# CP2102_UART.net
KiCad netlist of a schematic drawn in Altium Designer
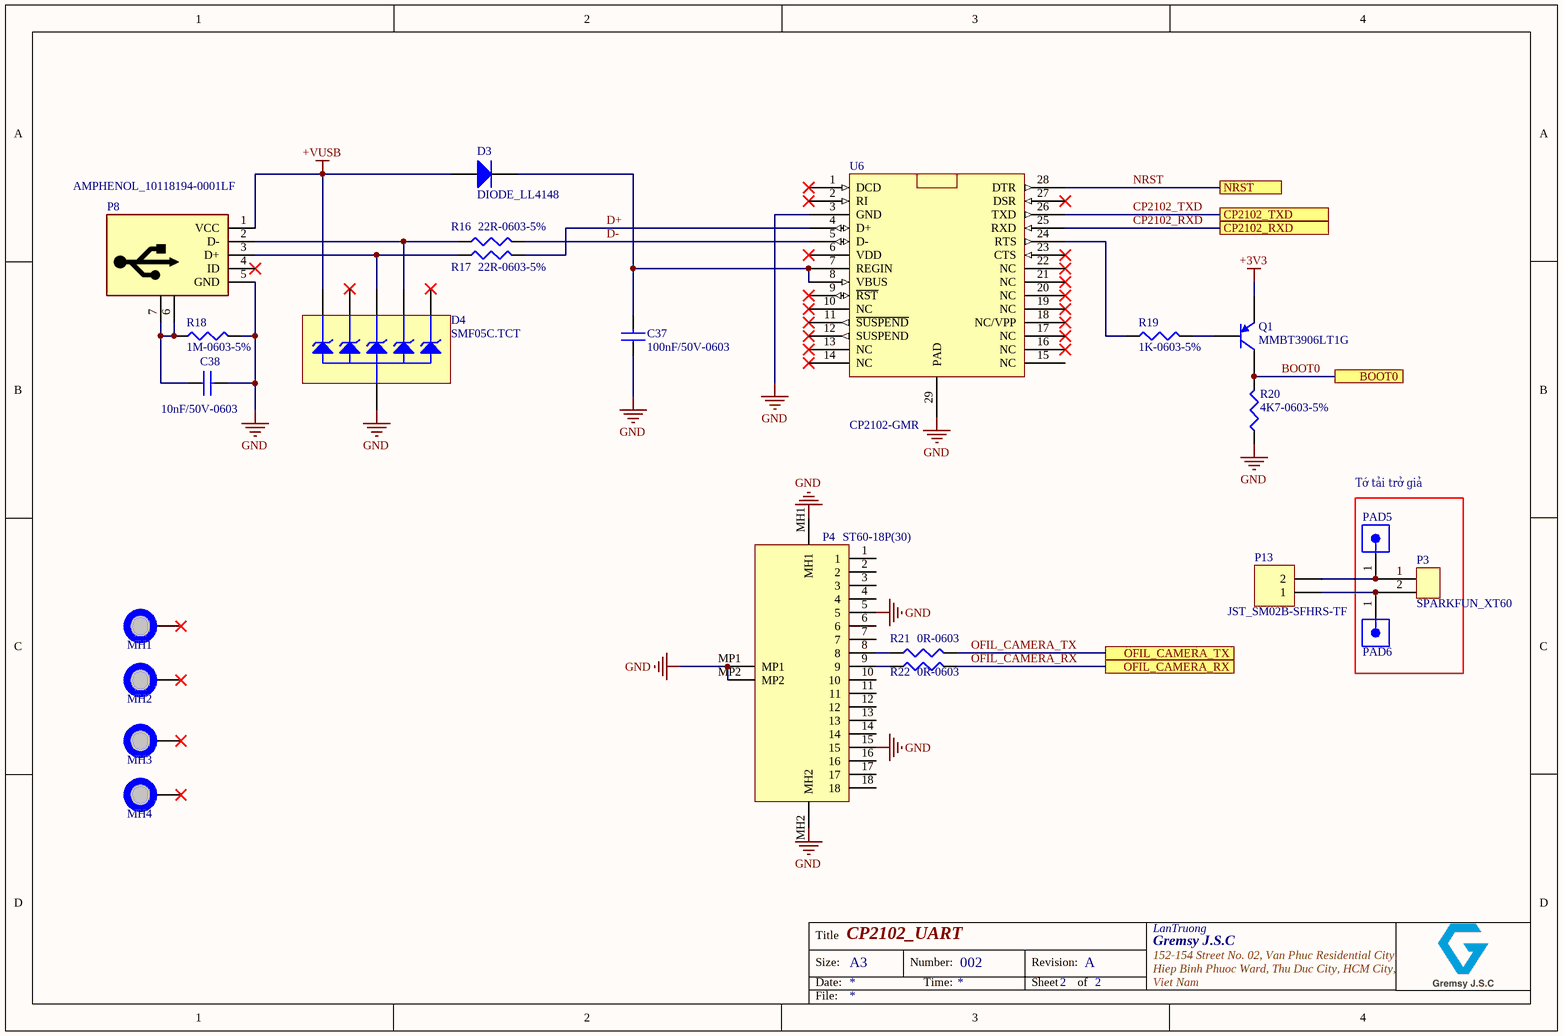
[diagram p0: CP2102_UART.SchDoc]

(export (version "E")
  (design (tool "Eeschema 10.0.6"))
  (components
    (comp (ref "C37")
      (value "100nF/50V-0603")
      (footprint "CAP0603")
      (description "CAP CER 0.1UF 50V X7R 0603")
      (fields (field (name "TOLERANCE") "±10%"))
      (libsource (lib "GremsyJSC") (part "CAP_100nF/50V-0603-10%"))
    )
    (comp (ref "C38")
      (value "10nF/50V-0603")
      (footprint "CAP0603")
      (description "CAP CER 10000PF 50V X7R 0603")
      (fields (field (name "TOLERANCE") "±10%"))
      (libsource (lib "GremsyJSC") (part "CAP_10nF/50V-0603-10%"))
    )
    (comp (ref "D3")
      (value "DIODE_LL4148")
      (footprint "SOD80")
      (description "DIODE GEN PURP 100V 200MA SOD80")
      (fields (field (name "MANUFACTURER") "Fairchild/ON Semiconductor"))
      (libsource (lib "GremsyJSC") (part "DIODE-RECTIFIER_LL4148"))
    )
    (comp (ref "D4")
      (value "SMF05C.TCT")
      (footprint "SC-88")
      (description "TVS DIODE 5VWM 12.5VC SC70-6")
      (libsource (lib "GremsyJSC") (part "DIODE-ESD_SMF05C.TCT"))
    )
    (comp (ref "MH1")
      (value "MH_3MMC_2.1MMD")
      (footprint "MH_3MMD_2.1MMD")
      (description "Mounting Hole 3mm Diameter, 2.1mm Drill")
      (libsource (lib "GremsyJSC") (part "MH_3MMC_2.1MMD"))
    )
    (comp (ref "MH2")
      (value "MH_3MMC_2.1MMD")
      (footprint "MH_3MMD_2.1MMD")
      (description "Mounting Hole 3mm Diameter, 2.1mm Drill")
      (libsource (lib "GremsyJSC") (part "MH_3MMC_2.1MMD"))
    )
    (comp (ref "MH3")
      (value "MH_3MMC_2.1MMD")
      (footprint "MH_3MMD_2.1MMD")
      (description "Mounting Hole 3mm Diameter, 2.1mm Drill")
      (libsource (lib "GremsyJSC") (part "MH_3MMC_2.1MMD"))
    )
    (comp (ref "MH4")
      (value "MH_3MMC_2.1MMD")
      (footprint "MH_3MMD_2.1MMD")
      (description "Mounting Hole 3mm Diameter, 2.1mm Drill")
      (libsource (lib "GremsyJSC") (part "MH_3MMC_2.1MMD"))
    )
    (comp (ref "P3")
      (value "SPARKFUN_XT60")
      (footprint "GremsyJSC:XT60_MALE_RA")
      (description "CON XT-60, MALE PIN, THROUGH HOLE, 500V, 30A")
      (fields (field (name "MANUFACTURER") "SparkFun Electronics"))
      (libsource (lib "GremsyJSC") (part "CON-SPARKFUN_XT60"))
    )
    (comp (ref "P4")
      (value "ST60-18P(30)")
      (footprint "GremsyJSC:ST6018P30")
      (description "HEADER 18POS PITCH 0.5MM, SMD, ST, FEMALE")
      (libsource (lib "GremsyJSC") (part "CON-HIROSE_ST60-18P(30)"))
    )
    (comp (ref "P8")
      (value "AMPHENOL_10118194-0001LF")
      (footprint "USB-B-Micro_10118194-0001LF")
      (description "USB2.0 MICRO_5POS-RA-SMD-F-AM, FEMALE")
      (libsource (lib "GremsyJSC") (part "CON-AMPHENOL_10118194-0001LF"))
    )
    (comp (ref "P13")
      (value "JST_SM02B-SFHRS-TF")
      (footprint "JST_M02B-SFHRS-TF(LF)(SN)")
      (description "PWR_2POS-P1.8-RA-SMD-M")
      (fields (field (name "MANUFACTURER") "JST"))
      (libsource (lib "GremsyJSC") (part "CON-JST_SM02B-SFHRS-TF"))
    )
    (comp (ref "PAD5")
      (value "PAD_2.5MM_1.5MM")
      (footprint "PAD_2.5MM_1.5MM_HOLE")
      (description "PAD_2.5MMC_1.5MMD_HOLE")
      (libsource (lib "GremsyJSC") (part "PAD_2.5MMC_1.5MMD_HOLE"))
    )
    (comp (ref "PAD6")
      (value "PAD_2.5MM_1.5MM")
      (footprint "PAD_2.5MM_1.5MM_HOLE")
      (description "PAD_2.5MMC_1.5MMD_HOLE")
      (libsource (lib "GremsyJSC") (part "PAD_2.5MMC_1.5MMD_HOLE"))
    )
    (comp (ref "Q1")
      (value "MMBT3906LT1G")
      (footprint "SOT23")
      (description "TRANS PNP 40V 0.2A SOT23")
      (fields (field (name "TOLERANCE") "±10%"))
      (libsource (lib "GremsyJSC") (part "TRNS-PNP_MMBT3906LT1G"))
    )
    (comp (ref "R16")
      (value "22R-0603-5%")
      (footprint "RES0603")
      (description "RES 22 OHM 5% 1/10W 0603")
      (fields (field (name "TOLERANCE") "±5%"))
      (libsource (lib "GremsyJSC") (part "RES_22R-0603-5%"))
    )
    (comp (ref "R17")
      (value "22R-0603-5%")
      (footprint "RES0603")
      (description "RES 22 OHM 5% 1/10W 0603")
      (fields (field (name "TOLERANCE") "±5%"))
      (libsource (lib "GremsyJSC") (part "RES_22R-0603-5%"))
    )
    (comp (ref "R18")
      (value "1M-0603-5%")
      (footprint "RES0603")
      (description "RES 1M OHM 5% 1/10W 0603")
      (fields (field (name "TOLERANCE") "±5%"))
      (libsource (lib "GremsyJSC") (part "RES_1M-0603-5%"))
    )
    (comp (ref "R19")
      (value "1K-0603-5%")
      (footprint "RES0603")
      (description "RES 1K OHM 5% 1/10W 0603")
      (fields (field (name "TOLERANCE") "±5%"))
      (libsource (lib "GremsyJSC") (part "RES_1K-0603-5%"))
    )
    (comp (ref "R20")
      (value "4K7-0603-5%")
      (footprint "RES0603")
      (description "RES 4.7K OHM 5% 1/10W 0603")
      (fields (field (name "MANUFACTURER") "Yageo") (field (name "TOLERANCE") "±5%"))
      (libsource (lib "GremsyJSC") (part "RES_4K7-0603-5%"))
    )
    (comp (ref "R21")
      (value "0R-0603")
      (footprint "RES0603")
      (description "RES 0 OHM JUMPER 1/10W 0603")
      (fields (field (name "TOLERANCE") "Jumper"))
      (libsource (lib "GremsyJSC") (part "RES_0R-0603"))
    )
    (comp (ref "R22")
      (value "0R-0603")
      (footprint "RES0603")
      (description "RES 0 OHM JUMPER 1/10W 0603")
      (fields (field (name "TOLERANCE") "Jumper"))
      (libsource (lib "GremsyJSC") (part "RES_0R-0603"))
    )
    (comp (ref "U6")
      (value "CP2102-GMR")
      (footprint "QFN28-Pitch 0.5 mm")
      (description "IC USB-TO-UART BRIDGE 28VQFN")
      (libsource (lib "GremsyCo") (part "CP2102-GMR"))
    )
  )
  (nets
    (net (code "1") (name "+3V3") (class "Default")
      (node (ref "Q1") (pin "2") (pinfunction "E_2") (pintype "passive"))
    )
    (net (code "2") (name "+VUSB") (class "Default")
      (node (ref "D3") (pin "1") (pinfunction "A_1") (pintype "passive"))
      (node (ref "D4") (pin "1") (pintype "passive"))
      (node (ref "P8") (pin "1") (pinfunction "VCC_1") (pintype "passive"))
    )
    (net (code "3") (name "/BOOT0") (class "Default")
      (node (ref "Q1") (pin "3") (pinfunction "C_3") (pintype "passive"))
      (node (ref "R20") (pin "2") (pinfunction "2_2") (pintype "passive"))
    )
    (net (code "4") (name "/CP2102_RXD") (class "Default")
      (node (ref "U6") (pin "25") (pinfunction "RXD_25") (pintype "input"))
    )
    (net (code "5") (name "/CP2102_TXD") (class "Default")
      (node (ref "U6") (pin "26") (pinfunction "TXD_26") (pintype "output"))
    )
    (net (code "6") (name "/D+") (class "Default")
      (node (ref "R17") (pin "2") (pinfunction "2_2") (pintype "passive"))
      (node (ref "U6") (pin "4") (pinfunction "D+_4") (pintype "bidirectional"))
    )
    (net (code "7") (name "/D-") (class "Default")
      (node (ref "R16") (pin "2") (pinfunction "2_2") (pintype "passive"))
      (node (ref "U6") (pin "5") (pinfunction "D-_5") (pintype "bidirectional"))
    )
    (net (code "8") (name "/NRST") (class "Default")
      (node (ref "U6") (pin "28") (pinfunction "DTR_28") (pintype "output"))
    )
    (net (code "9") (name "/OFIL_CAMERA_RX") (class "Default")
      (node (ref "R22") (pin "2") (pinfunction "2_2") (pintype "passive"))
    )
    (net (code "10") (name "/OFIL_CAMERA_TX") (class "Default")
      (node (ref "R21") (pin "2") (pinfunction "2_2") (pintype "passive"))
    )
    (net (code "11") (name "GND") (class "Default")
      (node (ref "C37") (pin "1") (pinfunction "1_1") (pintype "passive"))
      (node (ref "C38") (pin "2") (pinfunction "2_2") (pintype "passive"))
      (node (ref "D4") (pin "2") (pintype "passive"))
      (node (ref "P4") (pin "15") (pinfunction "15_15") (pintype "passive"))
      (node (ref "P4") (pin "5") (pinfunction "5_5") (pintype "passive"))
      (node (ref "P4") (pin "MH1") (pinfunction "MH1_MH1") (pintype "passive"))
      (node (ref "P4") (pin "MH2") (pinfunction "MH2_MH2") (pintype "passive"))
      (node (ref "P4") (pin "MP1") (pinfunction "MP1_MP1") (pintype "passive"))
      (node (ref "P4") (pin "MP2") (pinfunction "MP2_MP2") (pintype "passive"))
      (node (ref "P8") (pin "5") (pinfunction "GND_5") (pintype "passive"))
      (node (ref "R18") (pin "2") (pinfunction "2_2") (pintype "passive"))
      (node (ref "R20") (pin "1") (pinfunction "1_1") (pintype "passive"))
      (node (ref "U6") (pin "29") (pinfunction "PAD_29") (pintype "power_in"))
      (node (ref "U6") (pin "3") (pinfunction "GND_3") (pintype "power_in"))
    )
    (net (code "12") (name "Net-(C38-Pad1)") (class "Default")
      (node (ref "C38") (pin "1") (pinfunction "1_1") (pintype "passive"))
      (node (ref "P8") (pin "6") (pinfunction "SHIELD_6") (pintype "passive"))
      (node (ref "P8") (pin "7") (pinfunction "SHIELD_7") (pintype "power_in"))
      (node (ref "R18") (pin "1") (pinfunction "1_1") (pintype "passive"))
    )
    (net (code "13") (name "Net-(D3-K)") (class "Default")
      (node (ref "C37") (pin "2") (pinfunction "2_2") (pintype "passive"))
      (node (ref "D3") (pin "2") (pinfunction "K_2") (pintype "passive"))
      (node (ref "U6") (pin "7") (pinfunction "REGIN_7") (pintype "power_in"))
      (node (ref "U6") (pin "8") (pinfunction "VBUS_8") (pintype "input"))
    )
    (net (code "14") (name "Net-(P4-Pad8)") (class "Default")
      (node (ref "P4") (pin "8") (pinfunction "8_8") (pintype "passive"))
      (node (ref "R21") (pin "1") (pinfunction "1_1") (pintype "passive"))
    )
    (net (code "15") (name "Net-(P4-Pad9)") (class "Default")
      (node (ref "P4") (pin "9") (pinfunction "9_9") (pintype "passive"))
      (node (ref "R22") (pin "1") (pinfunction "1_1") (pintype "passive"))
    )
    (net (code "16") (name "Net-(P8-D+)") (class "Default")
      (node (ref "D4") (pin "4") (pintype "passive"))
      (node (ref "P8") (pin "3") (pinfunction "D+_3") (pintype "passive"))
      (node (ref "R17") (pin "1") (pinfunction "1_1") (pintype "passive"))
    )
    (net (code "17") (name "Net-(P8-D-)") (class "Default")
      (node (ref "D4") (pin "5") (pintype "passive"))
      (node (ref "P8") (pin "2") (pinfunction "D-_2") (pintype "passive"))
      (node (ref "R16") (pin "1") (pinfunction "1_1") (pintype "passive"))
    )
    (net (code "18") (name "Net-(P13-Pad1)") (class "Default")
      (node (ref "P13") (pin "1") (pinfunction "1_1") (pintype "passive"))
      (node (ref "P3") (pin "2") (pinfunction "2_2") (pintype "passive"))
      (node (ref "PAD6") (pin "1") (pinfunction "1_1") (pintype "passive"))
    )
    (net (code "19") (name "Net-(P13-Pad2)") (class "Default")
      (node (ref "P13") (pin "2") (pinfunction "2_2") (pintype "passive"))
      (node (ref "P3") (pin "1") (pinfunction "1_1") (pintype "passive"))
      (node (ref "PAD5") (pin "1") (pinfunction "1_1") (pintype "passive"))
    )
    (net (code "20") (name "Net-(Q1-B)") (class "Default")
      (node (ref "Q1") (pin "1") (pinfunction "B_1") (pintype "passive"))
      (node (ref "R19") (pin "2") (pinfunction "2_2") (pintype "passive"))
    )
    (net (code "21") (name "Net-(U6-RTS)") (class "Default")
      (node (ref "R19") (pin "1") (pinfunction "1_1") (pintype "passive"))
      (node (ref "U6") (pin "24") (pinfunction "RTS_24") (pintype "output"))
    )
    (net (code "22") (name "unconnected-(D4-Pad3)") (class "Default")
      (node (ref "D4") (pin "3") (pintype "passive+no_connect"))
    )
    (net (code "23") (name "unconnected-(D4-Pad6)") (class "Default")
      (node (ref "D4") (pin "6") (pintype "passive+no_connect"))
    )
    (net (code "24") (name "unconnected-(MH1-Pad1)") (class "Default")
      (node (ref "MH1") (pin "1") (pinfunction "1_1") (pintype "passive+no_connect"))
    )
    (net (code "25") (name "unconnected-(MH2-Pad1)") (class "Default")
      (node (ref "MH2") (pin "1") (pinfunction "1_1") (pintype "passive+no_connect"))
    )
    (net (code "26") (name "unconnected-(MH3-Pad1)") (class "Default")
      (node (ref "MH3") (pin "1") (pinfunction "1_1") (pintype "passive+no_connect"))
    )
    (net (code "27") (name "unconnected-(MH4-Pad1)") (class "Default")
      (node (ref "MH4") (pin "1") (pinfunction "1_1") (pintype "passive+no_connect"))
    )
    (net (code "28") (name "unconnected-(P4-Pad1)") (class "Default")
      (node (ref "P4") (pin "1") (pinfunction "1_1") (pintype "passive"))
    )
    (net (code "29") (name "unconnected-(P4-Pad2)") (class "Default")
      (node (ref "P4") (pin "2") (pinfunction "2_2") (pintype "passive"))
    )
    (net (code "30") (name "unconnected-(P4-Pad3)") (class "Default")
      (node (ref "P4") (pin "3") (pinfunction "3_3") (pintype "passive"))
    )
    (net (code "31") (name "unconnected-(P4-Pad4)") (class "Default")
      (node (ref "P4") (pin "4") (pinfunction "4_4") (pintype "passive"))
    )
    (net (code "32") (name "unconnected-(P4-Pad6)") (class "Default")
      (node (ref "P4") (pin "6") (pinfunction "6_6") (pintype "passive"))
    )
    (net (code "33") (name "unconnected-(P4-Pad7)") (class "Default")
      (node (ref "P4") (pin "7") (pinfunction "7_7") (pintype "passive"))
    )
    (net (code "34") (name "unconnected-(P4-Pad10)") (class "Default")
      (node (ref "P4") (pin "10") (pinfunction "10_10") (pintype "passive"))
    )
    (net (code "35") (name "unconnected-(P4-Pad11)") (class "Default")
      (node (ref "P4") (pin "11") (pinfunction "11_11") (pintype "passive"))
    )
    (net (code "36") (name "unconnected-(P4-Pad12)") (class "Default")
      (node (ref "P4") (pin "12") (pinfunction "12_12") (pintype "passive"))
    )
    (net (code "37") (name "unconnected-(P4-Pad13)") (class "Default")
      (node (ref "P4") (pin "13") (pinfunction "13_13") (pintype "passive"))
    )
    (net (code "38") (name "unconnected-(P4-Pad14)") (class "Default")
      (node (ref "P4") (pin "14") (pinfunction "14_14") (pintype "passive"))
    )
    (net (code "39") (name "unconnected-(P4-Pad16)") (class "Default")
      (node (ref "P4") (pin "16") (pinfunction "16_16") (pintype "passive"))
    )
    (net (code "40") (name "unconnected-(P4-Pad17)") (class "Default")
      (node (ref "P4") (pin "17") (pinfunction "17_17") (pintype "passive"))
    )
    (net (code "41") (name "unconnected-(P4-Pad18)") (class "Default")
      (node (ref "P4") (pin "18") (pinfunction "18_18") (pintype "passive"))
    )
    (net (code "42") (name "unconnected-(P8-ID-Pad4)") (class "Default")
      (node (ref "P8") (pin "4") (pinfunction "ID_4") (pintype "passive+no_connect"))
    )
    (net (code "43") (name "unconnected-(U6-CTS-Pad23)") (class "Default")
      (node (ref "U6") (pin "23") (pinfunction "CTS_23") (pintype "input+no_connect"))
    )
    (net (code "44") (name "unconnected-(U6-DCD-Pad1)") (class "Default")
      (node (ref "U6") (pin "1") (pinfunction "DCD_1") (pintype "input+no_connect"))
    )
    (net (code "45") (name "unconnected-(U6-DSR-Pad27)") (class "Default")
      (node (ref "U6") (pin "27") (pinfunction "DSR_27") (pintype "input+no_connect"))
    )
    (net (code "46") (name "unconnected-(U6-NC-Pad10)") (class "Default")
      (node (ref "U6") (pin "10") (pinfunction "NC_10") (pintype "passive+no_connect"))
    )
    (net (code "47") (name "unconnected-(U6-NC-Pad13)") (class "Default")
      (node (ref "U6") (pin "13") (pinfunction "NC_13") (pintype "passive+no_connect"))
    )
    (net (code "48") (name "unconnected-(U6-NC-Pad14)") (class "Default")
      (node (ref "U6") (pin "14") (pinfunction "NC_14") (pintype "passive+no_connect"))
    )
    (net (code "49") (name "unconnected-(U6-NC-Pad15)") (class "Default")
      (node (ref "U6") (pin "15") (pinfunction "NC_15") (pintype "passive"))
    )
    (net (code "50") (name "unconnected-(U6-NC-Pad16)") (class "Default")
      (node (ref "U6") (pin "16") (pinfunction "NC_16") (pintype "passive+no_connect"))
    )
    (net (code "51") (name "unconnected-(U6-NC-Pad17)") (class "Default")
      (node (ref "U6") (pin "17") (pinfunction "NC_17") (pintype "passive+no_connect"))
    )
    (net (code "52") (name "unconnected-(U6-NC-Pad19)") (class "Default")
      (node (ref "U6") (pin "19") (pinfunction "NC_19") (pintype "passive+no_connect"))
    )
    (net (code "53") (name "unconnected-(U6-NC-Pad20)") (class "Default")
      (node (ref "U6") (pin "20") (pinfunction "NC_20") (pintype "passive+no_connect"))
    )
    (net (code "54") (name "unconnected-(U6-NC-Pad21)") (class "Default")
      (node (ref "U6") (pin "21") (pinfunction "NC_21") (pintype "passive+no_connect"))
    )
    (net (code "55") (name "unconnected-(U6-NC-Pad22)") (class "Default")
      (node (ref "U6") (pin "22") (pinfunction "NC_22") (pintype "passive+no_connect"))
    )
    (net (code "56") (name "unconnected-(U6-NC{slash}VPP-Pad18)") (class "Default")
      (node (ref "U6") (pin "18") (pinfunction "NC/VPP_18") (pintype "passive+no_connect"))
    )
    (net (code "57") (name "unconnected-(U6-RI-Pad2)") (class "Default")
      (node (ref "U6") (pin "2") (pinfunction "RI_2") (pintype "input+no_connect"))
    )
    (net (code "58") (name "unconnected-(U6-SUSPEND-Pad12)") (class "Default")
      (node (ref "U6") (pin "12") (pinfunction "SUSPEND_12") (pintype "output+no_connect"))
    )
    (net (code "59") (name "unconnected-(U6-VDD-Pad6)") (class "Default")
      (node (ref "U6") (pin "6") (pinfunction "VDD_6") (pintype "power_in+no_connect"))
    )
    (net (code "60") (name "unconnected-(U6-~{RST}-Pad9)") (class "Default")
      (node (ref "U6") (pin "9") (pinfunction "~{RST}_9") (pintype "bidirectional+no_connect"))
    )
    (net (code "61") (name "unconnected-(U6-~{SUSPEND}-Pad11)") (class "Default")
      (node (ref "U6") (pin "11") (pinfunction "~{SUSPEND}_11") (pintype "output+no_connect"))
    )
  )
)
